# AduCM3555.net
KiCad netlist of a schematic drawn in Altium Designer
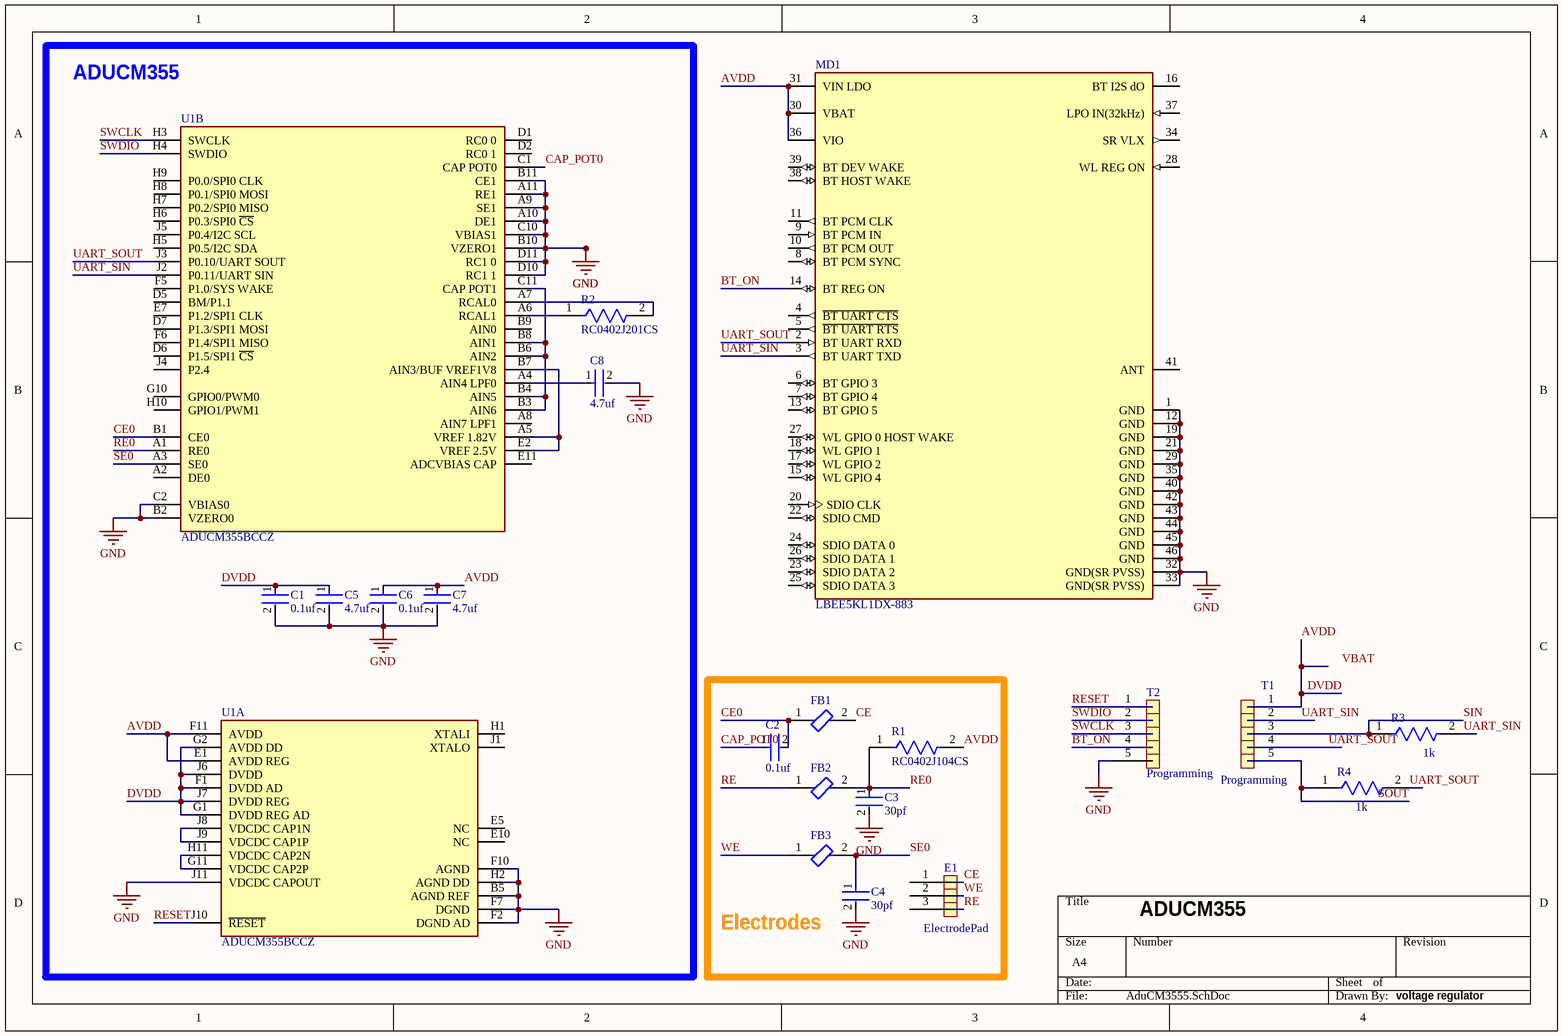
[diagram p0: AduCM3555.SchDoc]

(export (version "E")
  (design (tool "Eeschema 10.0.6"))
  (components
    (comp (ref "C1")
      (value "0.1uf")
      (footprint "FP-GRM022-0_02-MFG")
      (description "Chip Multilayer Ceramic Capacitors for General Purpose, 01005, 0.10uF, X5R, 15%, 20%, 6.3V")
      (fields (field (name "TOLERANCE") "20%"))
      (libsource (lib "Altium Content Vault") (part "02cd4be3c70576c341d710602a673aa"))
    )
    (comp (ref "C2")
      (value "0.1uf")
      (footprint "FP-GRM022-0_02-MFG")
      (description "Chip Multilayer Ceramic Capacitors for General Purpose, 01005, 0.10uF, X5R, 15%, 20%, 6.3V")
      (fields (field (name "TOLERANCE") "20%"))
      (libsource (lib "Altium Content Vault") (part "02cd4be3c70576c341d710602a673aa"))
    )
    (comp (ref "C3")
      (value "30pf")
      (footprint "FP-GRM022-0_02-MFG")
      (description "Chip Multilayer Ceramic Capacitors for General Purpose, 01005, 30pF, C0G, 30ppm/°C, 5%, 50V")
      (fields (field (name "TOLERANCE") "5%"))
      (libsource (lib "Altium Content Vault") (part "02cd4be3c70576c341d710602a673aa"))
    )
    (comp (ref "C4")
      (value "30pf")
      (footprint "FP-GRM022-0_02-MFG")
      (description "Chip Multilayer Ceramic Capacitors for General Purpose, 01005, 30pF, C0G, 30ppm/°C, 5%, 50V")
      (fields (field (name "TOLERANCE") "5%"))
      (libsource (lib "Altium Content Vault") (part "02cd4be3c70576c341d710602a673aa"))
    )
    (comp (ref "C5")
      (value "4.7uf")
      (footprint "FP-GRM155-0_1-MFG")
      (description "Chip Multilayer Ceramic Capacitors for General Purpose, 0402, 4.7uF, X5R, 15%, 20%, 6.3V")
      (fields (field (name "VOLTAGE") "6.3V") (field (name "TOLERANCE") "20%"))
      (libsource (lib "Altium Content Vault") (part "11868f565c42a9108669ba33697ecf6"))
    )
    (comp (ref "C6")
      (value "0.1uf")
      (footprint "FP-GRM022-0_02-MFG")
      (description "Chip Multilayer Ceramic Capacitors for General Purpose, 01005, 0.10uF, X5R, 15%, 20%, 6.3V")
      (fields (field (name "TOLERANCE") "20%"))
      (libsource (lib "Altium Content Vault") (part "02cd4be3c70576c341d710602a673aa"))
    )
    (comp (ref "C7")
      (value "4.7uf")
      (footprint "FP-GRM155-0_1-MFG")
      (description "Chip Multilayer Ceramic Capacitors for General Purpose, 0402, 4.7uF, X5R, 15%, 20%, 6.3V")
      (fields (field (name "VOLTAGE") "6.3V") (field (name "TOLERANCE") "20%"))
      (libsource (lib "Altium Content Vault") (part "11868f565c42a9108669ba33697ecf6"))
    )
    (comp (ref "C8")
      (value "4.7uf")
      (footprint "FP-GRM155-0_1-MFG")
      (description "Chip Multilayer Ceramic Capacitors for General Purpose, 0402, 4.7uF, X5R, 15%, 20%, 6.3V")
      (fields (field (name "VOLTAGE") "6.3V") (field (name "TOLERANCE") "20%"))
      (libsource (lib "Altium Content Vault") (part "11868f565c42a9108669ba33697ecf6"))
    )
    (comp (ref "E1")
      (value "ElectrodePad")
      (footprint "pad")
      (libsource (lib "Schlib1") (part "ElectrodePad"))
    )
    (comp (ref "FB1")
      (value "BLM15AG601SN1D")
      (footprint "FP-BLM15-0_05-MFG")
      (description "Chip Ferrite Bead, 0402, 600Ω @ 100MHz, 0.52Ω, 25%, 300mA")
      (fields (field (name "TOLERANCE") "25%"))
      (libsource (lib "Altium Content Vault") (part "5f30dd21d616792df468990f7003faa"))
    )
    (comp (ref "FB2")
      (value "BLM15AG601SN1D")
      (footprint "FP-BLM15-0_05-MFG")
      (description "Chip Ferrite Bead, 0402, 600Ω @ 100MHz, 0.52Ω, 25%, 300mA")
      (fields (field (name "TOLERANCE") "25%"))
      (libsource (lib "Altium Content Vault") (part "5f30dd21d616792df468990f7003faa"))
    )
    (comp (ref "FB3")
      (value "BLM15AG601SN1D")
      (footprint "FP-BLM15-0_05-MFG")
      (description "Chip Ferrite Bead, 0402, 600Ω @ 100MHz, 0.52Ω, 25%, 300mA")
      (fields (field (name "TOLERANCE") "25%"))
      (libsource (lib "Altium Content Vault") (part "5f30dd21d616792df468990f7003faa"))
    )
    (comp (ref "MD1")
      (value "LBEE5KL1DX-883")
      (footprint "FP-LBEE5KL1DX-883-MFG")
      (description "RF TXRX MOD BLUETOOTH/WIFI")
      (fields
        (field (name "OCTOPART") "https://octopart.com/lbee5kl1dx-883-murata-74182126")
        (field (name "MANUFACTURER") "Murata")
      )
      (libsource (lib "Altium Content Vault") (part "71e105902f48c5ebd8df9dd2546c2f1"))
    )
    (comp (ref "R1")
      (value "RC0402J104CS")
      (footprint "FP-RC0402-MFG")
      (description "Res Thick Film 01005 100kΩ 5% 0.03W ±250ppm/°C Molded SMD T/R")
      (fields (field (name "TOLERANCE") "5%"))
      (libsource (lib "Altium Content Vault") (part "1029c3af85768c4190bb7ad29bc67b5"))
    )
    (comp (ref "R2")
      (value "RC0402J201CS")
      (footprint "FP-RC0402-IPC_A")
      (description "Res Thick Film 01005 200Ω 5% 0.03W ±250ppm/°C Molded SMD T/R")
      (fields (field (name "TOLERANCE") "5%"))
      (libsource (lib "Altium Content Vault") (part "1029c3af85768c4190bb7ad29bc67b5"))
    )
    (comp (ref "R3")
      (value "1k")
      (footprint "FP-RC0402-MFG")
      (description "Res Thick Film 01005 1kΩ 5% 0.03W ±250ppm/°C Molded SMD T/R")
      (fields (field (name "TOLERANCE") "5%"))
      (libsource (lib "Altium Content Vault") (part "1029c3af85768c4190bb7ad29bc67b5"))
    )
    (comp (ref "R4")
      (value "1k")
      (footprint "FP-RC0402-MFG")
      (description "Res Thick Film 01005 1kΩ 5% 0.03W ±250ppm/°C Molded SMD T/R")
      (fields (field (name "TOLERANCE") "5%"))
      (libsource (lib "Altium Content Vault") (part "1029c3af85768c4190bb7ad29bc67b5"))
    )
    (comp (ref "T1")
      (value "Programming")
      (footprint "Programming")
      (libsource (lib "") (part "Programming_1"))
    )
    (comp (ref "T2")
      (value "Programming")
      (footprint "Programming")
      (libsource (lib "Schlib1") (part "Programming"))
    )
    (comp (ref "U1")
      (value "ADUCM355BCCZ")
      (footprint "FP-CC-72-2-MFG")
      (description "IC MCU 32BIT 128KB FLASH 72LGA")
      (libsource (lib "Altium Content Vault") (part "789a98f2e0fa9b97a049a75c327204c"))
    )
  )
  (nets
    (net (code "1") (name "/AVDD") (class "Default")
      (node (ref "C1") (pin "1") (pinfunction "1_1") (pintype "passive"))
      (node (ref "C5") (pin "1") (pinfunction "1_1") (pintype "passive"))
      (node (ref "C6") (pin "1") (pinfunction "1_1") (pintype "passive"))
      (node (ref "C7") (pin "1") (pinfunction "1_1") (pintype "passive"))
      (node (ref "MD1") (pin "30") (pinfunction "VBAT_30") (pintype "power_in"))
      (node (ref "MD1") (pin "31") (pinfunction "VIN_LDO_31") (pintype "power_in"))
      (node (ref "MD1") (pin "36") (pinfunction "VIO_36") (pintype "power_in"))
      (node (ref "R1") (pin "2") (pinfunction "2_2") (pintype "passive"))
      (node (ref "T1") (pin "1") (pintype "passive"))
      (node (ref "U1") (pin "E1") (pinfunction "AVDD_REG_E1") (pintype "passive"))
      (node (ref "U1") (pin "F1") (pinfunction "DVDD_AD_F1") (pintype "passive"))
      (node (ref "U1") (pin "F11") (pinfunction "AVDD_F11") (pintype "passive"))
      (node (ref "U1") (pin "G1") (pinfunction "DVDD_REG_AD_G1") (pintype "passive"))
      (node (ref "U1") (pin "G2") (pinfunction "AVDD_DD_G2") (pintype "passive"))
      (node (ref "U1") (pin "J6") (pinfunction "DVDD_J6") (pintype "passive"))
      (node (ref "U1") (pin "J7") (pinfunction "DVDD_REG_J7") (pintype "passive"))
    )
    (net (code "2") (name "/BT_ON") (class "Default")
      (node (ref "MD1") (pin "14") (pinfunction "BT_REG_ON_14") (pintype "bidirectional"))
      (node (ref "T2") (pin "4") (pintype "passive"))
    )
    (net (code "3") (name "/CAP_POT0") (class "Default")
      (node (ref "C2") (pin "1") (pinfunction "1_1") (pintype "passive"))
      (node (ref "U1") (pin "C1") (pinfunction "CAP_POT0_C1") (pintype "passive"))
    )
    (net (code "4") (name "/CE") (class "Default")
      (node (ref "E1") (pin "1") (pintype "passive"))
      (node (ref "FB1") (pin "2") (pinfunction "2_2") (pintype "passive"))
    )
    (net (code "5") (name "/CE0") (class "Default")
      (node (ref "C2") (pin "2") (pinfunction "2_2") (pintype "passive"))
      (node (ref "FB1") (pin "1") (pinfunction "1_1") (pintype "passive"))
      (node (ref "U1") (pin "B1") (pinfunction "CE0_B1") (pintype "passive"))
    )
    (net (code "6") (name "/RE") (class "Default")
      (node (ref "E1") (pin "3") (pintype "passive"))
      (node (ref "FB2") (pin "1") (pinfunction "1_1") (pintype "passive"))
    )
    (net (code "7") (name "/RE0") (class "Default")
      (node (ref "C3") (pin "1") (pinfunction "1_1") (pintype "passive"))
      (node (ref "FB2") (pin "2") (pinfunction "2_2") (pintype "passive"))
      (node (ref "R1") (pin "1") (pinfunction "1_1") (pintype "passive"))
      (node (ref "U1") (pin "A1") (pinfunction "RE0_A1") (pintype "passive"))
    )
    (net (code "8") (name "/RESET") (class "Default")
      (node (ref "T2") (pin "1") (pintype "passive"))
      (node (ref "U1") (pin "J10") (pinfunction "~{RESET}_J10") (pintype "passive"))
    )
    (net (code "9") (name "/SE0") (class "Default")
      (node (ref "C4") (pin "1") (pinfunction "1_1") (pintype "passive"))
      (node (ref "FB3") (pin "2") (pinfunction "2_2") (pintype "passive"))
      (node (ref "U1") (pin "A3") (pinfunction "SE0_A3") (pintype "passive"))
    )
    (net (code "10") (name "/SIN") (class "Default")
      (node (ref "R3") (pin "1") (pinfunction "1_1") (pintype "passive"))
      (node (ref "T1") (pin "3") (pintype "passive"))
    )
    (net (code "11") (name "/SOUT") (class "Default")
      (node (ref "R4") (pin "1") (pinfunction "1_1") (pintype "passive"))
      (node (ref "T1") (pin "5") (pintype "passive"))
    )
    (net (code "12") (name "/SWCLK") (class "Default")
      (node (ref "T2") (pin "3") (pintype "passive"))
      (node (ref "U1") (pin "H3") (pinfunction "SWCLK_H3") (pintype "passive"))
    )
    (net (code "13") (name "/SWDIO") (class "Default")
      (node (ref "T2") (pin "2") (pintype "passive"))
      (node (ref "U1") (pin "H4") (pinfunction "SWDIO_H4") (pintype "passive"))
    )
    (net (code "14") (name "/UART_SIN") (class "Default")
      (node (ref "MD1") (pin "3") (pinfunction "BT_UART_TXD_3") (pintype "output"))
      (node (ref "R3") (pin "2") (pinfunction "2_2") (pintype "passive"))
      (node (ref "T1") (pin "2") (pintype "passive"))
      (node (ref "U1") (pin "J2") (pinfunction "P0.11/UART_SIN_J2") (pintype "passive"))
    )
    (net (code "15") (name "/UART_SOUT") (class "Default")
      (node (ref "MD1") (pin "2") (pinfunction "BT_UART_RXD_2") (pintype "input"))
      (node (ref "R4") (pin "2") (pinfunction "2_2") (pintype "passive"))
      (node (ref "T1") (pin "4") (pintype "passive"))
      (node (ref "U1") (pin "J3") (pinfunction "P0.10/UART_SOUT_J3") (pintype "passive"))
    )
    (net (code "17") (name "/WE") (class "Default")
      (node (ref "E1") (pin "2") (pintype "passive"))
      (node (ref "FB3") (pin "1") (pinfunction "1_1") (pintype "passive"))
    )
    (net (code "18") (name "GND") (class "Default")
      (node (ref "C1") (pin "2") (pinfunction "2_2") (pintype "passive"))
      (node (ref "C3") (pin "2") (pinfunction "2_2") (pintype "passive"))
      (node (ref "C4") (pin "2") (pinfunction "2_2") (pintype "passive"))
      (node (ref "C5") (pin "2") (pinfunction "2_2") (pintype "passive"))
      (node (ref "C6") (pin "2") (pinfunction "2_2") (pintype "passive"))
      (node (ref "C7") (pin "2") (pinfunction "2_2") (pintype "passive"))
      (node (ref "C8") (pin "2") (pinfunction "2_2") (pintype "passive"))
      (node (ref "MD1") (pin "1") (pinfunction "GND_1") (pintype "power_in"))
      (node (ref "MD1") (pin "12") (pinfunction "GND_12") (pintype "power_in"))
      (node (ref "MD1") (pin "19") (pinfunction "GND_19") (pintype "power_in"))
      (node (ref "MD1") (pin "21") (pinfunction "GND_21") (pintype "power_in"))
      (node (ref "MD1") (pin "29") (pinfunction "GND_29") (pintype "power_in"))
      (node (ref "MD1") (pin "32") (pinfunction "GND(SR_PVSS)_32") (pintype "power_in"))
      (node (ref "MD1") (pin "33") (pinfunction "GND(SR_PVSS)_33") (pintype "power_in"))
      (node (ref "MD1") (pin "35") (pinfunction "GND_35") (pintype "power_in"))
      (node (ref "MD1") (pin "40") (pinfunction "GND_40") (pintype "power_in"))
      (node (ref "MD1") (pin "42") (pinfunction "GND_42") (pintype "power_in"))
      (node (ref "MD1") (pin "43") (pinfunction "GND_43") (pintype "power_in"))
      (node (ref "MD1") (pin "44") (pinfunction "GND_44") (pintype "power_in"))
      (node (ref "MD1") (pin "45") (pinfunction "GND_45") (pintype "power_in"))
      (node (ref "MD1") (pin "46") (pinfunction "GND_46") (pintype "power_in"))
      (node (ref "U1") (pin "A10") (pinfunction "DE1_A10") (pintype "passive"))
      (node (ref "U1") (pin "A11") (pinfunction "RE1_A11") (pintype "passive"))
      (node (ref "U1") (pin "A9") (pinfunction "SE1_A9") (pintype "passive"))
      (node (ref "U1") (pin "B10") (pinfunction "VZERO1_B10") (pintype "passive"))
      (node (ref "U1") (pin "B11") (pinfunction "CE1_B11") (pintype "passive"))
      (node (ref "U1") (pin "B2") (pinfunction "VZERO0_B2") (pintype "passive"))
      (node (ref "U1") (pin "B5") (pinfunction "AGND_REF_B5") (pintype "passive"))
      (node (ref "U1") (pin "C10") (pinfunction "VBIAS1_C10") (pintype "passive"))
      (node (ref "U1") (pin "C2") (pinfunction "VBIAS0_C2") (pintype "passive"))
      (node (ref "U1") (pin "D10") (pinfunction "RC1_1_D10") (pintype "passive"))
      (node (ref "U1") (pin "D11") (pinfunction "RC1_0_D11") (pintype "passive"))
      (node (ref "U1") (pin "F10") (pinfunction "AGND_F10") (pintype "passive"))
      (node (ref "U1") (pin "F2") (pinfunction "DGND_AD_F2") (pintype "passive"))
      (node (ref "U1") (pin "F7") (pinfunction "DGND_F7") (pintype "passive"))
      (node (ref "U1") (pin "H2") (pinfunction "AGND_DD_H2") (pintype "passive"))
      (node (ref "U1") (pin "J11") (pinfunction "VDCDC_CAPOUT_J11") (pintype "passive"))
    )
    (net (code "19") (name "Net-(U1A-VDCDC_CAP1N)") (class "Default")
      (node (ref "U1") (pin "J8") (pinfunction "VDCDC_CAP1N_J8") (pintype "passive"))
      (node (ref "U1") (pin "J9") (pinfunction "VDCDC_CAP1P_J9") (pintype "passive"))
    )
    (net (code "20") (name "Net-(U1A-VDCDC_CAP2N)") (class "Default")
      (node (ref "U1") (pin "G11") (pinfunction "VDCDC_CAP2P_G11") (pintype "passive"))
      (node (ref "U1") (pin "H11") (pinfunction "VDCDC_CAP2N_H11") (pintype "passive"))
    )
    (net (code "21") (name "Net-(U1B-AIN1)") (class "Default")
      (node (ref "U1") (pin "B3") (pinfunction "AIN6_B3") (pintype "passive"))
      (node (ref "U1") (pin "B4") (pinfunction "AIN5_B4") (pintype "passive"))
      (node (ref "U1") (pin "B6") (pinfunction "AIN2_B6") (pintype "passive"))
      (node (ref "U1") (pin "B8") (pinfunction "AIN1_B8") (pintype "passive"))
      (node (ref "U1") (pin "C11") (pinfunction "CAP_POT1_C11") (pintype "passive"))
    )
    (net (code "22") (name "Net-(U1B-AIN3{slash}BUF_VREF1V8)") (class "Default")
      (node (ref "U1") (pin "A5") (pinfunction "VREF_1.82V_A5") (pintype "passive"))
      (node (ref "U1") (pin "B7") (pinfunction "AIN3/BUF_VREF1V8_B7") (pintype "passive"))
      (node (ref "U1") (pin "E2") (pinfunction "VREF_2.5V_E2") (pintype "passive"))
    )
    (net (code "23") (name "Net-(U1B-AIN4_LPF0)") (class "Default")
      (node (ref "C8") (pin "1") (pinfunction "1_1") (pintype "passive"))
      (node (ref "U1") (pin "A4") (pinfunction "AIN4_LPF0_A4") (pintype "passive"))
    )
    (net (code "24") (name "Net-(U1B-RCAL0)") (class "Default")
      (node (ref "R2") (pin "2") (pinfunction "2_2") (pintype "passive"))
      (node (ref "U1") (pin "A7") (pinfunction "RCAL0_A7") (pintype "passive"))
    )
    (net (code "25") (name "Net-(U1B-RCAL1)") (class "Default")
      (node (ref "R2") (pin "1") (pinfunction "1_1") (pintype "passive"))
      (node (ref "U1") (pin "A6") (pinfunction "RCAL1_A6") (pintype "passive"))
    )
    (net (code "26") (name "unconnected-(MD1-ANT-Pad41)") (class "Default")
      (node (ref "MD1") (pin "41") (pinfunction "ANT_41") (pintype "passive"))
    )
    (net (code "27") (name "unconnected-(MD1-BT_DEV_WAKE-Pad39)") (class "Default")
      (node (ref "MD1") (pin "39") (pinfunction "BT_DEV_WAKE_39") (pintype "bidirectional"))
    )
    (net (code "28") (name "unconnected-(MD1-BT_GPIO_3-Pad6)") (class "Default")
      (node (ref "MD1") (pin "6") (pinfunction "BT_GPIO_3_6") (pintype "bidirectional"))
    )
    (net (code "29") (name "unconnected-(MD1-BT_GPIO_4-Pad7)") (class "Default")
      (node (ref "MD1") (pin "7") (pinfunction "BT_GPIO_4_7") (pintype "bidirectional"))
    )
    (net (code "30") (name "unconnected-(MD1-BT_GPIO_5-Pad13)") (class "Default")
      (node (ref "MD1") (pin "13") (pinfunction "BT_GPIO_5_13") (pintype "bidirectional"))
    )
    (net (code "31") (name "unconnected-(MD1-BT_HOST_WAKE-Pad38)") (class "Default")
      (node (ref "MD1") (pin "38") (pinfunction "BT_HOST_WAKE_38") (pintype "bidirectional"))
    )
    (net (code "32") (name "unconnected-(MD1-BT_I2S_dO-Pad16)") (class "Default")
      (node (ref "MD1") (pin "16") (pinfunction "BT_I2S_dO_16") (pintype "passive"))
    )
    (net (code "33") (name "unconnected-(MD1-BT_PCM_CLK-Pad11)") (class "Default")
      (node (ref "MD1") (pin "11") (pinfunction "BT_PCM_CLK_11") (pintype "output"))
    )
    (net (code "34") (name "unconnected-(MD1-BT_PCM_IN-Pad9)") (class "Default")
      (node (ref "MD1") (pin "9") (pinfunction "BT_PCM_IN_9") (pintype "input"))
    )
    (net (code "35") (name "unconnected-(MD1-BT_PCM_OUT-Pad10)") (class "Default")
      (node (ref "MD1") (pin "10") (pinfunction "BT_PCM_OUT_10") (pintype "output"))
    )
    (net (code "36") (name "unconnected-(MD1-BT_PCM_SYNC-Pad8)") (class "Default")
      (node (ref "MD1") (pin "8") (pinfunction "BT_PCM_SYNC_8") (pintype "bidirectional"))
    )
    (net (code "37") (name "unconnected-(MD1-LPO_IN(32kHz)-Pad37)") (class "Default")
      (node (ref "MD1") (pin "37") (pinfunction "LPO_IN(32kHz)_37") (pintype "input"))
    )
    (net (code "38") (name "unconnected-(MD1-SDIO_CLK-Pad20)") (class "Default")
      (node (ref "MD1") (pin "20") (pinfunction "SDIO_CLK_20") (pintype "input"))
    )
    (net (code "39") (name "unconnected-(MD1-SDIO_CMD-Pad22)") (class "Default")
      (node (ref "MD1") (pin "22") (pinfunction "SDIO_CMD_22") (pintype "bidirectional"))
    )
    (net (code "40") (name "unconnected-(MD1-SDIO_DATA_0-Pad24)") (class "Default")
      (node (ref "MD1") (pin "24") (pinfunction "SDIO_DATA_0_24") (pintype "bidirectional"))
    )
    (net (code "41") (name "unconnected-(MD1-SDIO_DATA_1-Pad26)") (class "Default")
      (node (ref "MD1") (pin "26") (pinfunction "SDIO_DATA_1_26") (pintype "bidirectional"))
    )
    (net (code "42") (name "unconnected-(MD1-SDIO_DATA_2-Pad23)") (class "Default")
      (node (ref "MD1") (pin "23") (pinfunction "SDIO_DATA_2_23") (pintype "bidirectional"))
    )
    (net (code "43") (name "unconnected-(MD1-SDIO_DATA_3-Pad25)") (class "Default")
      (node (ref "MD1") (pin "25") (pinfunction "SDIO_DATA_3_25") (pintype "bidirectional"))
    )
    (net (code "44") (name "unconnected-(MD1-SR_VLX-Pad34)") (class "Default")
      (node (ref "MD1") (pin "34") (pinfunction "SR_VLX_34") (pintype "output"))
    )
    (net (code "45") (name "unconnected-(MD1-WL_GPIO_0_HOST_WAKE-Pad27)") (class "Default")
      (node (ref "MD1") (pin "27") (pinfunction "WL_GPIO_0_HOST_WAKE_27") (pintype "bidirectional"))
    )
    (net (code "46") (name "unconnected-(MD1-WL_GPIO_1-Pad18)") (class "Default")
      (node (ref "MD1") (pin "18") (pinfunction "WL_GPIO_1_18") (pintype "bidirectional"))
    )
    (net (code "47") (name "unconnected-(MD1-WL_GPIO_2-Pad17)") (class "Default")
      (node (ref "MD1") (pin "17") (pinfunction "WL_GPIO_2_17") (pintype "bidirectional"))
    )
    (net (code "48") (name "unconnected-(MD1-WL_GPIO_4-Pad15)") (class "Default")
      (node (ref "MD1") (pin "15") (pinfunction "WL_GPIO_4_15") (pintype "bidirectional"))
    )
    (net (code "49") (name "unconnected-(MD1-WL_REG_ON-Pad28)") (class "Default")
      (node (ref "MD1") (pin "28") (pinfunction "WL_REG_ON_28") (pintype "input"))
    )
    (net (code "50") (name "unconnected-(MD1-~{BT_UART_CTS}-Pad4)") (class "Default")
      (node (ref "MD1") (pin "4") (pinfunction "~{BT_UART_CTS}_4") (pintype "output"))
    )
    (net (code "51") (name "unconnected-(MD1-~{BT_UART_RTS}-Pad5)") (class "Default")
      (node (ref "MD1") (pin "5") (pinfunction "~{BT_UART_RTS}_5") (pintype "output"))
    )
    (net (code "52") (name "unconnected-(T2-Pad5)") (class "Default")
      (node (ref "T2") (pin "5") (pintype "passive"))
    )
    (net (code "53") (name "unconnected-(U1A-NC-PadE5)") (class "Default")
      (node (ref "U1") (pin "E5") (pinfunction "NC_E5") (pintype "passive"))
    )
    (net (code "54") (name "unconnected-(U1A-NC-PadE10)") (class "Default")
      (node (ref "U1") (pin "E10") (pinfunction "NC_E10") (pintype "passive"))
    )
    (net (code "55") (name "unconnected-(U1A-XTALI-PadH1)") (class "Default")
      (node (ref "U1") (pin "H1") (pinfunction "XTALI_H1") (pintype "passive"))
    )
    (net (code "56") (name "unconnected-(U1A-XTALO-PadJ1)") (class "Default")
      (node (ref "U1") (pin "J1") (pinfunction "XTALO_J1") (pintype "passive"))
    )
    (net (code "57") (name "unconnected-(U1B-ADCVBIAS_CAP-PadE11)") (class "Default")
      (node (ref "U1") (pin "E11") (pinfunction "ADCVBIAS_CAP_E11") (pintype "passive"))
    )
    (net (code "58") (name "unconnected-(U1B-AIN0-PadB9)") (class "Default")
      (node (ref "U1") (pin "B9") (pinfunction "AIN0_B9") (pintype "passive"))
    )
    (net (code "59") (name "unconnected-(U1B-AIN7_LPF1-PadA8)") (class "Default")
      (node (ref "U1") (pin "A8") (pinfunction "AIN7_LPF1_A8") (pintype "passive"))
    )
    (net (code "60") (name "unconnected-(U1B-BM{slash}P1.1-PadD5)") (class "Default")
      (node (ref "U1") (pin "D5") (pinfunction "BM/P1.1_D5") (pintype "passive"))
    )
    (net (code "61") (name "unconnected-(U1B-DE0-PadA2)") (class "Default")
      (node (ref "U1") (pin "A2") (pinfunction "DE0_A2") (pintype "passive"))
    )
    (net (code "62") (name "unconnected-(U1B-GPIO0{slash}PWM0-PadG10)") (class "Default")
      (node (ref "U1") (pin "G10") (pinfunction "GPIO0/PWM0_G10") (pintype "passive"))
    )
    (net (code "63") (name "unconnected-(U1B-GPIO1{slash}PWM1-PadH10)") (class "Default")
      (node (ref "U1") (pin "H10") (pinfunction "GPIO1/PWM1_H10") (pintype "passive"))
    )
    (net (code "64") (name "unconnected-(U1B-P0.0{slash}SPI0_CLK-PadH9)") (class "Default")
      (node (ref "U1") (pin "H9") (pinfunction "P0.0/SPI0_CLK_H9") (pintype "passive"))
    )
    (net (code "65") (name "unconnected-(U1B-P0.1{slash}SPI0_MOSI-PadH8)") (class "Default")
      (node (ref "U1") (pin "H8") (pinfunction "P0.1/SPI0_MOSI_H8") (pintype "passive"))
    )
    (net (code "66") (name "unconnected-(U1B-P0.2{slash}SPI0_MISO-PadH7)") (class "Default")
      (node (ref "U1") (pin "H7") (pinfunction "P0.2/SPI0_MISO_H7") (pintype "passive"))
    )
    (net (code "67") (name "unconnected-(U1B-P0.3{slash}SPI0_~{CS}-PadH6)") (class "Default")
      (node (ref "U1") (pin "H6") (pinfunction "P0.3/SPI0_~{CS}_H6") (pintype "passive"))
    )
    (net (code "68") (name "unconnected-(U1B-P0.4{slash}I2C_SCL-PadJ5)") (class "Default")
      (node (ref "U1") (pin "J5") (pinfunction "P0.4/I2C_SCL_J5") (pintype "passive"))
    )
    (net (code "69") (name "unconnected-(U1B-P0.5{slash}I2C_SDA-PadH5)") (class "Default")
      (node (ref "U1") (pin "H5") (pinfunction "P0.5/I2C_SDA_H5") (pintype "passive"))
    )
    (net (code "70") (name "unconnected-(U1B-P1.0{slash}SYS_WAKE-PadF5)") (class "Default")
      (node (ref "U1") (pin "F5") (pinfunction "P1.0/SYS_WAKE_F5") (pintype "passive"))
    )
    (net (code "71") (name "unconnected-(U1B-P1.2{slash}SPI1_CLK-PadE7)") (class "Default")
      (node (ref "U1") (pin "E7") (pinfunction "P1.2/SPI1_CLK_E7") (pintype "passive"))
    )
    (net (code "72") (name "unconnected-(U1B-P1.3{slash}SPI1_MOSI-PadD7)") (class "Default")
      (node (ref "U1") (pin "D7") (pinfunction "P1.3/SPI1_MOSI_D7") (pintype "passive"))
    )
    (net (code "73") (name "unconnected-(U1B-P1.4{slash}SPI1_MISO-PadF6)") (class "Default")
      (node (ref "U1") (pin "F6") (pinfunction "P1.4/SPI1_MISO_F6") (pintype "passive"))
    )
    (net (code "74") (name "unconnected-(U1B-P1.5{slash}SPI1_~{CS}-PadD6)") (class "Default")
      (node (ref "U1") (pin "D6") (pinfunction "P1.5/SPI1_~{CS}_D6") (pintype "passive"))
    )
    (net (code "75") (name "unconnected-(U1B-P2.4-PadJ4)") (class "Default")
      (node (ref "U1") (pin "J4") (pinfunction "P2.4_J4") (pintype "passive"))
    )
    (net (code "76") (name "unconnected-(U1B-RC0_0-PadD1)") (class "Default")
      (node (ref "U1") (pin "D1") (pinfunction "RC0_0_D1") (pintype "passive"))
    )
    (net (code "77") (name "unconnected-(U1B-RC0_1-PadD2)") (class "Default")
      (node (ref "U1") (pin "D2") (pinfunction "RC0_1_D2") (pintype "passive"))
    )
  )
)
